# SparkFun_dToF-TMF8820.net
KiCad netlist of a schematic drawn in EAGLE
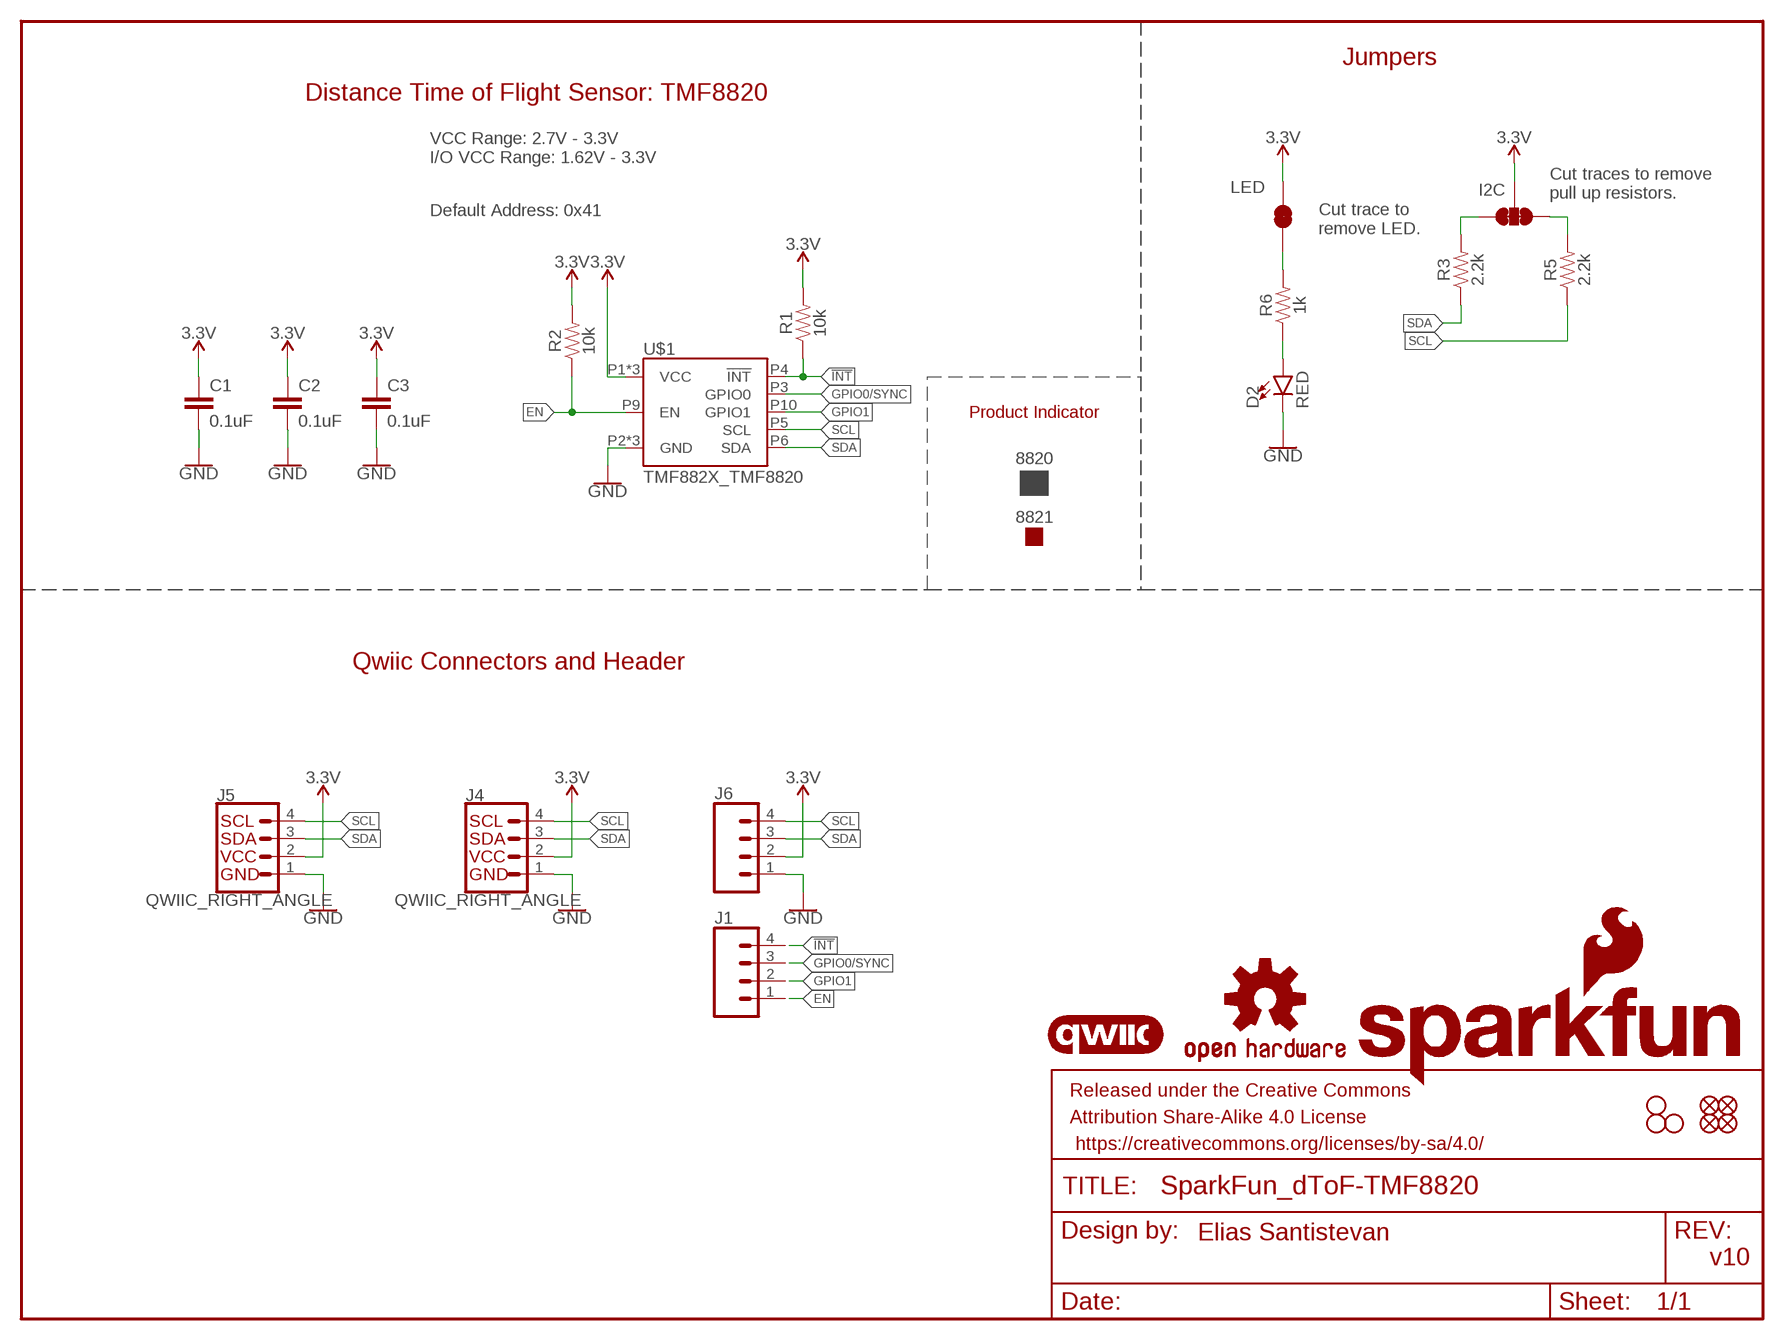
[diagram p0: schematic, sheet 1]

(export (version "E")
  (design (tool "Eeschema 10.0.6"))
  (components
    (comp (ref "8820")
      (value "PROD_ID_PASTE_SILK")
      (footprint "eagle-import:PRODUCT_IDENT_PASTE_SILK")
      (libsource (lib "eagle-import") (part "PROD_ID_PASTE_SILK"))
    )
    (comp (ref "8821")
      (value "PROD_ID_NO-PASTE_SILK")
      (footprint "eagle-import:PRODUCT_IDENT_NO_SILK")
      (libsource (lib "eagle-import") (part "PROD_ID_NO-PASTE_SILK"))
    )
    (comp (ref "C1")
      (value "0.1uF")
      (footprint "eagle-import:0402-TIGHT")
      (libsource (lib "eagle-import") (part "0.1UF-0402T-6.3V-10%-X7R"))
    )
    (comp (ref "C2")
      (value "0.1uF")
      (footprint "eagle-import:0402-TIGHT")
      (libsource (lib "eagle-import") (part "0.1UF-0402T-6.3V-10%-X7R"))
    )
    (comp (ref "C3")
      (value "0.1uF")
      (footprint "eagle-import:0402-TIGHT")
      (libsource (lib "eagle-import") (part "0.1UF-0402T-6.3V-10%-X7R"))
    )
    (comp (ref "D2")
      (value "RED")
      (footprint "eagle-import:LED-0603")
      (libsource (lib "eagle-import") (part "LED-RED0603"))
    )
    (comp (ref "FD5")
      (value "FIDUCIALUFIDUCIAL")
      (footprint "eagle-import:FIDUCIAL-MICRO")
      (libsource (lib "eagle-import") (part "FIDUCIALUFIDUCIAL"))
    )
    (comp (ref "FD6")
      (value "FIDUCIALUFIDUCIAL")
      (footprint "eagle-import:FIDUCIAL-MICRO")
      (libsource (lib "eagle-import") (part "FIDUCIALUFIDUCIAL"))
    )
    (comp (ref "FD7")
      (value "FIDUCIALUFIDUCIAL")
      (footprint "eagle-import:FIDUCIAL-MICRO")
      (libsource (lib "eagle-import") (part "FIDUCIALUFIDUCIAL"))
    )
    (comp (ref "FD8")
      (value "FIDUCIALUFIDUCIAL")
      (footprint "eagle-import:FIDUCIAL-MICRO")
      (libsource (lib "eagle-import") (part "FIDUCIALUFIDUCIAL"))
    )
    (comp (ref "FRAME2")
      (value "FRAME-LETTER")
      (footprint "eagle-import:CREATIVE_COMMONS")
      (libsource (lib "eagle-import") (part "FRAME-LETTER"))
    )
    (comp (ref "H5")
      (value "STAND-OFFTIGHT")
      (footprint "eagle-import:STAND-OFF-TIGHT")
      (libsource (lib "eagle-import") (part "STAND-OFFTIGHT"))
    )
    (comp (ref "H6")
      (value "STAND-OFFTIGHT")
      (footprint "eagle-import:STAND-OFF-TIGHT")
      (libsource (lib "eagle-import") (part "STAND-OFFTIGHT"))
    )
    (comp (ref "H8")
      (value "STAND-OFFTIGHT")
      (footprint "eagle-import:STAND-OFF-TIGHT")
      (libsource (lib "eagle-import") (part "STAND-OFFTIGHT"))
    )
    (comp (ref "I2C")
      (value "I2C_PU")
      (footprint "eagle-import:SMT-JUMPER_3_2-NC_TRACE_SILK")
      (libsource (lib "eagle-import") (part "JUMPER-SMT_3_2-NC_TRACE_SILK"))
    )
    (comp (ref "J1")
      (value "CONN_041X04_NO_SILK_NO_POP")
      (footprint "eagle-import:1X04_NO_SILK")
      (libsource (lib "eagle-import") (part "CONN_041X04_NO_SILK_NO_POP"))
    )
    (comp (ref "J4")
      (value "QWIIC_RIGHT_ANGLE")
      (footprint "eagle-import:JST04_1MM_RA")
      (libsource (lib "eagle-import") (part "QWIIC_CONNECTORJS-1MM"))
    )
    (comp (ref "J5")
      (value "QWIIC_RIGHT_ANGLE")
      (footprint "eagle-import:JST04_1MM_RA")
      (libsource (lib "eagle-import") (part "QWIIC_CONNECTORJS-1MM"))
    )
    (comp (ref "J6")
      (value "CONN_041X04_NO_SILK")
      (footprint "eagle-import:1X04_NO_SILK")
      (libsource (lib "eagle-import") (part "CONN_041X04_NO_SILK"))
    )
    (comp (ref "LED")
      (value "LED")
      (footprint "eagle-import:SMT-JUMPER_2_NC_TRACE_SILK")
      (libsource (lib "eagle-import") (part "JUMPER-SMT_2_NC_TRACE_SILK"))
    )
    (comp (ref "LOGO3")
      (value "SFE_LOGO_NAME_FLAME.1_INCH")
      (footprint "eagle-import:SFE_LOGO_NAME_FLAME_.1")
      (libsource (lib "eagle-import") (part "SFE_LOGO_NAME_FLAME.1_INCH"))
    )
    (comp (ref "LOGO4")
      (value "OSHW-LOGOS")
      (footprint "eagle-import:OSHW-LOGO-S")
      (libsource (lib "eagle-import") (part "OSHW-LOGOS"))
    )
    (comp (ref "R1")
      (value "10k")
      (footprint "eagle-import:0603")
      (libsource (lib "eagle-import") (part "10KOHM-0603-1/10W-1%"))
    )
    (comp (ref "R2")
      (value "10k")
      (footprint "eagle-import:0603")
      (libsource (lib "eagle-import") (part "10KOHM-0603-1/10W-1%"))
    )
    (comp (ref "R3")
      (value "2.2k")
      (footprint "eagle-import:0603")
      (libsource (lib "eagle-import") (part "2.2KOHM-0603-1/10W-1%"))
    )
    (comp (ref "R5")
      (value "2.2k")
      (footprint "eagle-import:0603")
      (libsource (lib "eagle-import") (part "2.2KOHM-0603-1/10W-1%"))
    )
    (comp (ref "R6")
      (value "1k")
      (footprint "eagle-import:0603")
      (libsource (lib "eagle-import") (part "1KOHM-0603-1/10W-1%"))
    )
    (comp (ref "U$1")
      (value "TMF882X_TMF8820")
      (footprint "eagle-import:TMF882X")
      (libsource (lib "eagle-import") (part "TMF882X_TMF8820"))
    )
    (comp (ref "U$6")
      (value "QWIIC_LOGO_5MM")
      (footprint "eagle-import:QWIIC_5MM")
      (libsource (lib "eagle-import") (part "QWIIC_LOGO_5MM"))
    )
  )
  (nets
    (net (code "1") (name "/~{INT}") (class "Default")
      (node (ref "J1") (pin "4") (pinfunction "4_4") (pintype "passive"))
      (node (ref "R1") (pin "1") (pinfunction "1_1") (pintype "passive"))
      (node (ref "U$1") (pin "P4") (pinfunction "~{INT}_P4") (pintype "bidirectional"))
    )
    (net (code "2") (name "3.3V") (class "Default")
      (node (ref "C1") (pin "1") (pinfunction "1_1") (pintype "passive"))
      (node (ref "C2") (pin "1") (pinfunction "1_1") (pintype "passive"))
      (node (ref "C3") (pin "1") (pinfunction "1_1") (pintype "passive"))
      (node (ref "I2C") (pin "2") (pinfunction "2_2") (pintype "passive"))
      (node (ref "J4") (pin "2") (pinfunction "2_2") (pintype "power_in"))
      (node (ref "J5") (pin "2") (pinfunction "2_2") (pintype "power_in"))
      (node (ref "J6") (pin "2") (pinfunction "2_2") (pintype "passive"))
      (node (ref "LED") (pin "2") (pinfunction "2_2") (pintype "passive"))
      (node (ref "R1") (pin "2") (pinfunction "2_2") (pintype "passive"))
      (node (ref "R2") (pin "2") (pinfunction "2_2") (pintype "passive"))
      (node (ref "U$1") (pin "P1") (pinfunction "VCC_P1") (pintype "power_in"))
      (node (ref "U$1") (pin "P12") (pinfunction "VCC_P12") (pintype "power_in"))
      (node (ref "U$1") (pin "P7") (pinfunction "VCC_P7") (pintype "power_in"))
    )
    (net (code "3") (name "EN") (class "Default")
      (node (ref "J1") (pin "1") (pinfunction "1_1") (pintype "passive"))
      (node (ref "R2") (pin "1") (pinfunction "1_1") (pintype "passive"))
      (node (ref "U$1") (pin "P9") (pinfunction "EN_P9") (pintype "input"))
    )
    (net (code "4") (name "GND") (class "Default")
      (node (ref "C1") (pin "2") (pinfunction "2_2") (pintype "passive"))
      (node (ref "C2") (pin "2") (pinfunction "2_2") (pintype "passive"))
      (node (ref "C3") (pin "2") (pinfunction "2_2") (pintype "passive"))
      (node (ref "D2") (pin "C") (pinfunction "C_C") (pintype "passive"))
      (node (ref "J4") (pin "1") (pinfunction "1_1") (pintype "power_in"))
      (node (ref "J5") (pin "1") (pinfunction "1_1") (pintype "power_in"))
      (node (ref "J6") (pin "1") (pinfunction "1_1") (pintype "passive"))
      (node (ref "U$1") (pin "P11") (pinfunction "GND_P11") (pintype "power_in"))
      (node (ref "U$1") (pin "P2") (pinfunction "GND_P2") (pintype "power_in"))
      (node (ref "U$1") (pin "P8") (pinfunction "GND_P8") (pintype "power_in"))
    )
    (net (code "5") (name "GPIO0{slash}SYNC") (class "Default")
      (node (ref "J1") (pin "3") (pinfunction "3_3") (pintype "passive"))
      (node (ref "U$1") (pin "P3") (pinfunction "GPIO0_P3") (pintype "bidirectional"))
    )
    (net (code "6") (name "GPIO1") (class "Default")
      (node (ref "J1") (pin "2") (pinfunction "2_2") (pintype "passive"))
      (node (ref "U$1") (pin "P10") (pinfunction "GPIO1_P10") (pintype "bidirectional"))
    )
    (net (code "7") (name "Net-(D2-PadA)") (class "Default")
      (node (ref "D2") (pin "A") (pinfunction "A_A") (pintype "passive"))
      (node (ref "R6") (pin "1") (pinfunction "1_1") (pintype "passive"))
    )
    (net (code "8") (name "Net-(I2C-Pad1)") (class "Default")
      (node (ref "I2C") (pin "1") (pinfunction "1_1") (pintype "passive"))
      (node (ref "R5") (pin "2") (pinfunction "2_2") (pintype "passive"))
    )
    (net (code "9") (name "Net-(I2C-Pad3)") (class "Default")
      (node (ref "I2C") (pin "3") (pinfunction "3_3") (pintype "passive"))
      (node (ref "R3") (pin "2") (pinfunction "2_2") (pintype "passive"))
    )
    (net (code "10") (name "Net-(LED-Pad1)") (class "Default")
      (node (ref "LED") (pin "1") (pinfunction "1_1") (pintype "passive"))
      (node (ref "R6") (pin "2") (pinfunction "2_2") (pintype "passive"))
    )
    (net (code "11") (name "SCL") (class "Default")
      (node (ref "J4") (pin "4") (pinfunction "4_4") (pintype "passive"))
      (node (ref "J5") (pin "4") (pinfunction "4_4") (pintype "passive"))
      (node (ref "J6") (pin "4") (pinfunction "4_4") (pintype "passive"))
      (node (ref "R5") (pin "1") (pinfunction "1_1") (pintype "passive"))
      (node (ref "U$1") (pin "P5") (pinfunction "SCL_P5") (pintype "bidirectional"))
    )
    (net (code "12") (name "SDA") (class "Default")
      (node (ref "J4") (pin "3") (pinfunction "3_3") (pintype "passive"))
      (node (ref "J5") (pin "3") (pinfunction "3_3") (pintype "passive"))
      (node (ref "J6") (pin "3") (pinfunction "3_3") (pintype "passive"))
      (node (ref "R3") (pin "1") (pinfunction "1_1") (pintype "passive"))
      (node (ref "U$1") (pin "P6") (pinfunction "SDA_P6") (pintype "bidirectional"))
    )
  )
)
